# Badge_Fancy.net
KiCad netlist of a schematic drawn in EAGLE
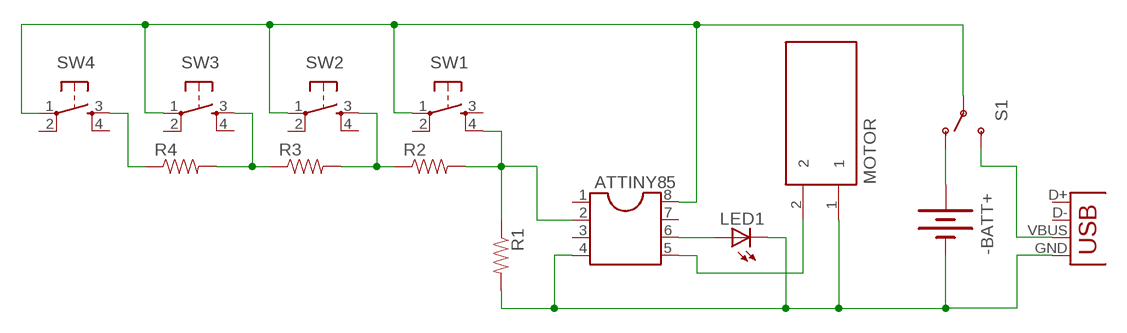
[diagram p0: schematic, sheet 1]

(export (version "E")
  (design (tool "Eeschema 10.0.6"))
  (components
    (comp (ref "-BATT+")
      (value "BATTERY245MM")
      (footprint "eagle-import:BATTCON_245MM")
      (libsource (lib "eagle-import") (part "BATTERY245MM"))
    )
    (comp (ref "ATTINY85")
      (value "DIL8S")
      (footprint "eagle-import:SOCKET-08")
      (libsource (lib "eagle-import") (part "DIL8S"))
    )
    (comp (ref "LED1")
      (value "LEDCHIPLED_0805")
      (footprint "eagle-import:CHIPLED_0805")
      (libsource (lib "eagle-import") (part "LEDCHIPLED_0805"))
    )
    (comp (ref "MOTOR")
      (value "VIB-MOTOR")
      (footprint "eagle-import:VIB-MOTOR")
      (libsource (lib "eagle-import") (part "VIB-MOTOR"))
    )
    (comp (ref "R1")
      (value "RESISTOR2010")
      (footprint "eagle-import:R2010")
      (libsource (lib "eagle-import") (part "RESISTOR2010"))
    )
    (comp (ref "R2")
      (value "RESISTOR2010")
      (footprint "eagle-import:R2010")
      (libsource (lib "eagle-import") (part "RESISTOR2010"))
    )
    (comp (ref "R3")
      (value "RESISTOR2010")
      (footprint "eagle-import:R2010")
      (libsource (lib "eagle-import") (part "RESISTOR2010"))
    )
    (comp (ref "R4")
      (value "RESISTOR2010")
      (footprint "eagle-import:R2010")
      (libsource (lib "eagle-import") (part "RESISTOR2010"))
    )
    (comp (ref "S1")
      (value "SWITCH-SPSTSMD")
      (footprint "eagle-import:AYZ0202")
      (libsource (lib "eagle-import") (part "SWITCH-SPSTSMD"))
    )
    (comp (ref "SW1")
      (value "TAC_SWITCHPTH")
      (footprint "eagle-import:TACTILE-PTH")
      (libsource (lib "eagle-import") (part "TAC_SWITCHPTH"))
    )
    (comp (ref "SW2")
      (value "TAC_SWITCHPTH")
      (footprint "eagle-import:TACTILE-PTH")
      (libsource (lib "eagle-import") (part "TAC_SWITCHPTH"))
    )
    (comp (ref "SW3")
      (value "TAC_SWITCHPTH")
      (footprint "eagle-import:TACTILE-PTH")
      (libsource (lib "eagle-import") (part "TAC_SWITCHPTH"))
    )
    (comp (ref "SW4")
      (value "TAC_SWITCHPTH")
      (footprint "eagle-import:TACTILE-PTH")
      (libsource (lib "eagle-import") (part "TAC_SWITCHPTH"))
    )
    (comp (ref "X2")
      (value "USBSMD")
      (footprint "eagle-import:USB-MINIB")
      (libsource (lib "eagle-import") (part "USBSMD"))
    )
  )
  (nets
    (net (code "1") (name "Net-(-BATT+-+)") (class "Default")
      (node (ref "-BATT+") (pin "1") (pinfunction "+_1") (pintype "power_in"))
      (node (ref "S1") (pin "1") (pinfunction "O_1") (pintype "passive"))
    )
    (net (code "2") (name "Net-(-BATT+--)") (class "Default")
      (node (ref "-BATT+") (pin "2") (pinfunction "-_2") (pintype "power_in"))
      (node (ref "ATTINY85") (pin "4") (pinfunction "4_4") (pintype "passive"))
      (node (ref "LED1") (pin "C") (pinfunction "C_C") (pintype "passive"))
      (node (ref "MOTOR") (pin "1") (pinfunction "1_1") (pintype "bidirectional"))
      (node (ref "R1") (pin "2") (pinfunction "2_2") (pintype "passive"))
      (node (ref "X2") (pin "GND") (pinfunction "GND_GND") (pintype "bidirectional"))
    )
    (net (code "3") (name "Net-(ATTINY85-Pad2)") (class "Default")
      (node (ref "ATTINY85") (pin "2") (pinfunction "2_2") (pintype "passive"))
      (node (ref "R1") (pin "1") (pinfunction "1_1") (pintype "passive"))
      (node (ref "R2") (pin "2") (pinfunction "2_2") (pintype "passive"))
      (node (ref "SW1") (pin "4") (pinfunction "4_4") (pintype "passive"))
    )
    (net (code "4") (name "Net-(ATTINY85-Pad5)") (class "Default")
      (node (ref "ATTINY85") (pin "5") (pinfunction "5_5") (pintype "passive"))
      (node (ref "MOTOR") (pin "2") (pinfunction "2_2") (pintype "bidirectional"))
    )
    (net (code "5") (name "Net-(ATTINY85-Pad6)") (class "Default")
      (node (ref "ATTINY85") (pin "6") (pinfunction "6_6") (pintype "passive"))
      (node (ref "LED1") (pin "A") (pinfunction "A_A") (pintype "passive"))
    )
    (net (code "6") (name "Net-(R2-Pad1)") (class "Default")
      (node (ref "R2") (pin "1") (pinfunction "1_1") (pintype "passive"))
      (node (ref "R3") (pin "2") (pinfunction "2_2") (pintype "passive"))
      (node (ref "SW2") (pin "3") (pinfunction "3_3") (pintype "passive"))
    )
    (net (code "7") (name "Net-(R3-Pad1)") (class "Default")
      (node (ref "R3") (pin "1") (pinfunction "1_1") (pintype "passive"))
      (node (ref "R4") (pin "2") (pinfunction "2_2") (pintype "passive"))
      (node (ref "SW3") (pin "3") (pinfunction "3_3") (pintype "passive"))
    )
    (net (code "8") (name "Net-(R4-Pad1)") (class "Default")
      (node (ref "R4") (pin "1") (pinfunction "1_1") (pintype "passive"))
      (node (ref "SW4") (pin "3") (pinfunction "3_3") (pintype "passive"))
    )
    (net (code "9") (name "Net-(S1-P)") (class "Default")
      (node (ref "ATTINY85") (pin "8") (pinfunction "8_8") (pintype "passive"))
      (node (ref "S1") (pin "2") (pinfunction "P_2") (pintype "passive"))
      (node (ref "SW1") (pin "1") (pinfunction "1_1") (pintype "passive"))
      (node (ref "SW2") (pin "1") (pinfunction "1_1") (pintype "passive"))
      (node (ref "SW3") (pin "1") (pinfunction "1_1") (pintype "passive"))
      (node (ref "SW4") (pin "1") (pinfunction "1_1") (pintype "passive"))
    )
    (net (code "10") (name "Net-(S1-S)") (class "Default")
      (node (ref "S1") (pin "3") (pinfunction "S_3") (pintype "passive"))
      (node (ref "X2") (pin "VBUS") (pinfunction "VBUS_VBUS") (pintype "bidirectional"))
    )
    (net (code "11") (name "unconnected-(ATTINY85-Pad1)") (class "Default")
      (node (ref "ATTINY85") (pin "1") (pinfunction "1_1") (pintype "passive"))
    )
    (net (code "12") (name "unconnected-(ATTINY85-Pad3)") (class "Default")
      (node (ref "ATTINY85") (pin "3") (pinfunction "3_3") (pintype "passive"))
    )
    (net (code "13") (name "unconnected-(ATTINY85-Pad7)") (class "Default")
      (node (ref "ATTINY85") (pin "7") (pinfunction "7_7") (pintype "passive"))
    )
    (net (code "14") (name "unconnected-(SW1-Pad2)") (class "Default")
      (node (ref "SW1") (pin "2") (pinfunction "2_2") (pintype "passive"))
    )
    (net (code "15") (name "unconnected-(SW1-Pad3)") (class "Default")
      (node (ref "SW1") (pin "3") (pinfunction "3_3") (pintype "passive"))
    )
    (net (code "16") (name "unconnected-(SW2-Pad2)") (class "Default")
      (node (ref "SW2") (pin "2") (pinfunction "2_2") (pintype "passive"))
    )
    (net (code "17") (name "unconnected-(SW2-Pad4)") (class "Default")
      (node (ref "SW2") (pin "4") (pinfunction "4_4") (pintype "passive"))
    )
    (net (code "18") (name "unconnected-(SW3-Pad2)") (class "Default")
      (node (ref "SW3") (pin "2") (pinfunction "2_2") (pintype "passive"))
    )
    (net (code "19") (name "unconnected-(SW3-Pad4)") (class "Default")
      (node (ref "SW3") (pin "4") (pinfunction "4_4") (pintype "passive"))
    )
    (net (code "20") (name "unconnected-(SW4-Pad2)") (class "Default")
      (node (ref "SW4") (pin "2") (pinfunction "2_2") (pintype "passive"))
    )
    (net (code "21") (name "unconnected-(SW4-Pad4)") (class "Default")
      (node (ref "SW4") (pin "4") (pinfunction "4_4") (pintype "passive"))
    )
    (net (code "22") (name "unconnected-(X2-PadD+)") (class "Default")
      (node (ref "X2") (pin "D+") (pinfunction "D+_D+") (pintype "bidirectional"))
    )
    (net (code "23") (name "unconnected-(X2-PadD-)") (class "Default")
      (node (ref "X2") (pin "D-") (pinfunction "D-_D-") (pintype "bidirectional"))
    )
  )
)
